# SRAM_Flash.net
KiCad netlist of a schematic drawn in Altium Designer
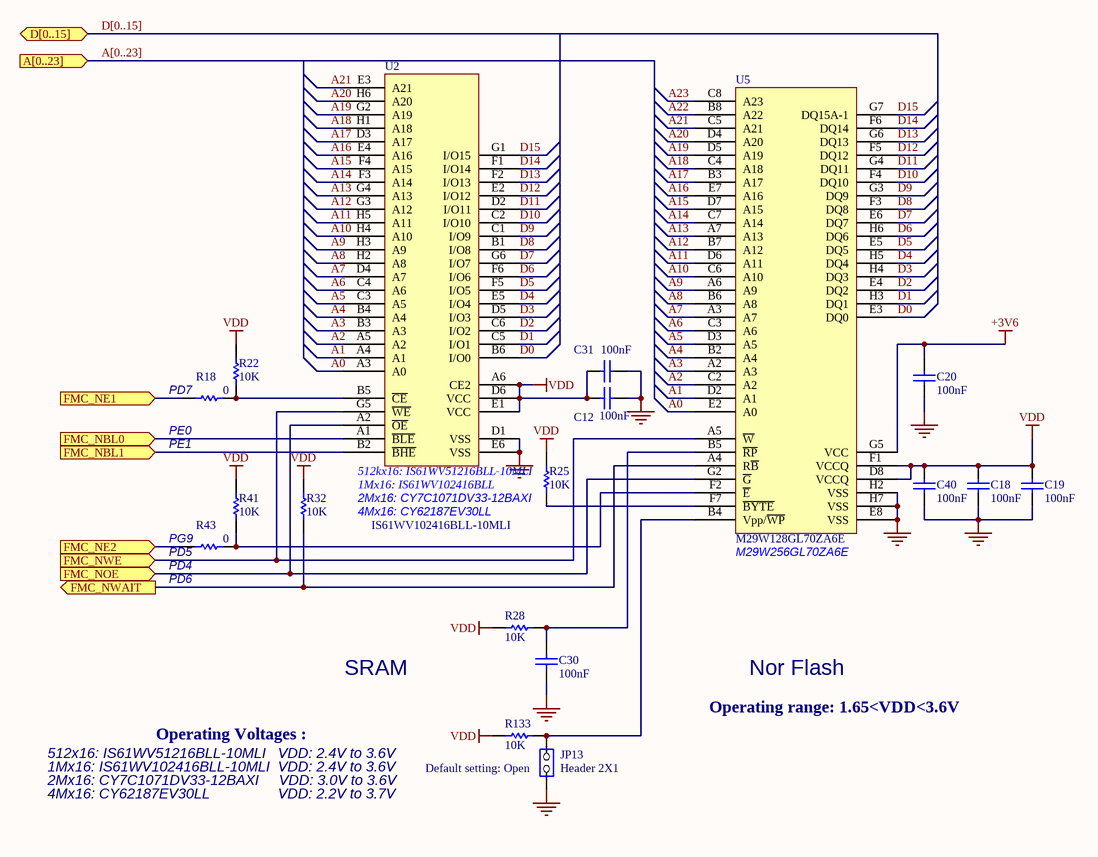
[diagram p0: SRAM&Flash.SchDoc]

(export (version "E")
  (design (tool "Eeschema 10.0.6"))
  (components
    (comp (ref "C12")
      (value "100nF")
      (footprint "0402C")
      (description "Capacitor")
      (fields (field (name "PUBLISHER") "Altium Limited"))
      (libsource (lib "Miscellaneous Devices") (part "Cap"))
    )
    (comp (ref "C18")
      (value "100nF")
      (footprint "0402C")
      (description "Capacitor")
      (fields (field (name "PUBLISHER") "Altium Limited"))
      (libsource (lib "Miscellaneous Devices") (part "Cap"))
    )
    (comp (ref "C19")
      (value "100nF")
      (footprint "0402C")
      (description "Capacitor")
      (fields (field (name "PUBLISHER") "Altium Limited"))
      (libsource (lib "Miscellaneous Devices") (part "Cap"))
    )
    (comp (ref "C20")
      (value "100nF")
      (footprint "0402C")
      (description "Capacitor")
      (fields (field (name "PUBLISHER") "Altium Limited"))
      (libsource (lib "Miscellaneous Devices") (part "Cap"))
    )
    (comp (ref "C30")
      (value "100nF")
      (footprint "0402C")
      (description "Capacitor")
      (fields (field (name "PUBLISHER") "Altium Limited"))
      (libsource (lib "Miscellaneous Devices") (part "Cap"))
    )
    (comp (ref "C31")
      (value "100nF")
      (footprint "0402C")
      (description "Capacitor")
      (fields (field (name "PUBLISHER") "Altium Limited"))
      (libsource (lib "Miscellaneous Devices") (part "Cap"))
    )
    (comp (ref "C40")
      (value "100nF")
      (footprint "0402C")
      (description "Capacitor")
      (fields (field (name "PUBLISHER") "Altium Limited"))
      (libsource (lib "Miscellaneous Devices") (part "Cap"))
    )
    (comp (ref "JP13") (value "Header 2X1") (footprint "SIP2") (libsource (lib "*") (part "JP2")))
    (comp (ref "R18")
      (value "0")
      (footprint "0603R")
      (description "Resistor")
      (fields (field (name "PUBLISHER") "Altium Limited"))
      (libsource (lib "Miscellaneous Devices") (part "Res1"))
    )
    (comp (ref "R22")
      (value "10K")
      (footprint "0402R")
      (description "Resistor")
      (fields (field (name "PUBLISHER") "Altium Limited"))
      (libsource (lib "Miscellaneous Devices") (part "res1"))
    )
    (comp (ref "R25")
      (value "10K")
      (footprint "0402R")
      (description "Resistor")
      (fields (field (name "PUBLISHER") "Altium Limited"))
      (libsource (lib "Miscellaneous Devices") (part "res1"))
    )
    (comp (ref "R28")
      (value "10K")
      (footprint "0402R")
      (description "Resistor")
      (fields (field (name "PUBLISHER") "Altium Limited"))
      (libsource (lib "Miscellaneous Devices") (part "res1"))
    )
    (comp (ref "R32")
      (value "10K")
      (footprint "0402R")
      (description "Resistor")
      (fields (field (name "PUBLISHER") "Altium Limited"))
      (libsource (lib "Miscellaneous Devices") (part "res1"))
    )
    (comp (ref "R41")
      (value "10K")
      (footprint "0402R")
      (description "Resistor")
      (fields (field (name "PUBLISHER") "Altium Limited"))
      (libsource (lib "Miscellaneous Devices") (part "res1"))
    )
    (comp (ref "R43")
      (value "0")
      (footprint "0603R")
      (description "Resistor")
      (fields (field (name "PUBLISHER") "Altium Limited"))
      (libsource (lib "Miscellaneous Devices") (part "Res1"))
    )
    (comp (ref "R133")
      (value "10K")
      (footprint "0402R")
      (description "Resistor")
      (fields (field (name "PUBLISHER") "Altium Limited"))
      (libsource (lib "Miscellaneous Devices") (part "res1"))
    )
    (comp (ref "U2")
      (value "IS61WV102416BLL-10MLI")
      (footprint "BGA48_0R75_9X11")
      (libsource (lib "MB1144_4") (part "SRAM_4Mx16"))
    )
    (comp (ref "U5")
      (value "M29W128GL70ZA6E")
      (footprint "BGA64_1_10X13")
      (libsource (lib "MB964") (part "M29W128FL70ZA6E"))
    )
  )
  (nets
    (net (code "1") (name "+3V6") (class "Default")
      (node (ref "C20") (pin "1") (pinfunction "1_1") (pintype "passive"))
      (node (ref "U5") (pin "G5") (pinfunction "VCC_G5") (pintype "passive"))
    )
    (net (code "2") (name "/A0") (class "Default")
      (node (ref "U2") (pin "A3") (pinfunction "A0_A3") (pintype "passive"))
      (node (ref "U5") (pin "E2") (pinfunction "A0_E2") (pintype "passive"))
    )
    (net (code "3") (name "/A1") (class "Default")
      (node (ref "U2") (pin "A4") (pinfunction "A1_A4") (pintype "passive"))
      (node (ref "U5") (pin "D2") (pinfunction "A1_D2") (pintype "passive"))
    )
    (net (code "4") (name "/A2") (class "Default")
      (node (ref "U2") (pin "A5") (pinfunction "A2_A5") (pintype "passive"))
      (node (ref "U5") (pin "C2") (pinfunction "A2_C2") (pintype "passive"))
    )
    (net (code "5") (name "/A3") (class "Default")
      (node (ref "U2") (pin "B3") (pinfunction "A3_B3") (pintype "passive"))
      (node (ref "U5") (pin "A2") (pinfunction "A3_A2") (pintype "passive"))
    )
    (net (code "6") (name "/A4") (class "Default")
      (node (ref "U2") (pin "B4") (pinfunction "A4_B4") (pintype "passive"))
      (node (ref "U5") (pin "B2") (pinfunction "A4_B2") (pintype "passive"))
    )
    (net (code "7") (name "/A5") (class "Default")
      (node (ref "U2") (pin "C3") (pinfunction "A5_C3") (pintype "passive"))
      (node (ref "U5") (pin "D3") (pinfunction "A5_D3") (pintype "passive"))
    )
    (net (code "8") (name "/A6") (class "Default")
      (node (ref "U2") (pin "C4") (pinfunction "A6_C4") (pintype "passive"))
      (node (ref "U5") (pin "C3") (pinfunction "A6_C3") (pintype "passive"))
    )
    (net (code "9") (name "/A7") (class "Default")
      (node (ref "U2") (pin "D4") (pinfunction "A7_D4") (pintype "passive"))
      (node (ref "U5") (pin "A3") (pinfunction "A7_A3") (pintype "passive"))
    )
    (net (code "10") (name "/A8") (class "Default")
      (node (ref "U2") (pin "H2") (pinfunction "A8_H2") (pintype "passive"))
      (node (ref "U5") (pin "B6") (pinfunction "A8_B6") (pintype "passive"))
    )
    (net (code "11") (name "/A9") (class "Default")
      (node (ref "U2") (pin "H3") (pinfunction "A9_H3") (pintype "passive"))
      (node (ref "U5") (pin "A6") (pinfunction "A9_A6") (pintype "passive"))
    )
    (net (code "12") (name "/A10") (class "Default")
      (node (ref "U2") (pin "H4") (pinfunction "A10_H4") (pintype "passive"))
      (node (ref "U5") (pin "C6") (pinfunction "A10_C6") (pintype "passive"))
    )
    (net (code "13") (name "/A11") (class "Default")
      (node (ref "U2") (pin "H5") (pinfunction "A11_H5") (pintype "passive"))
      (node (ref "U5") (pin "D6") (pinfunction "A11_D6") (pintype "passive"))
    )
    (net (code "14") (name "/A12") (class "Default")
      (node (ref "U2") (pin "G3") (pinfunction "A12_G3") (pintype "passive"))
      (node (ref "U5") (pin "B7") (pinfunction "A12_B7") (pintype "passive"))
    )
    (net (code "15") (name "/A13") (class "Default")
      (node (ref "U2") (pin "G4") (pinfunction "A13_G4") (pintype "passive"))
      (node (ref "U5") (pin "A7") (pinfunction "A13_A7") (pintype "passive"))
    )
    (net (code "16") (name "/A14") (class "Default")
      (node (ref "U2") (pin "F3") (pinfunction "A14_F3") (pintype "passive"))
      (node (ref "U5") (pin "C7") (pinfunction "A14_C7") (pintype "passive"))
    )
    (net (code "17") (name "/A15") (class "Default")
      (node (ref "U2") (pin "F4") (pinfunction "A15_F4") (pintype "passive"))
      (node (ref "U5") (pin "D7") (pinfunction "A15_D7") (pintype "passive"))
    )
    (net (code "18") (name "/A16") (class "Default")
      (node (ref "U2") (pin "E4") (pinfunction "A16_E4") (pintype "passive"))
      (node (ref "U5") (pin "E7") (pinfunction "A16_E7") (pintype "passive"))
    )
    (net (code "19") (name "/A17") (class "Default")
      (node (ref "U2") (pin "D3") (pinfunction "A17_D3") (pintype "passive"))
      (node (ref "U5") (pin "B3") (pinfunction "A17_B3") (pintype "passive"))
    )
    (net (code "20") (name "/A18") (class "Default")
      (node (ref "U2") (pin "H1") (pinfunction "A18_H1") (pintype "passive"))
      (node (ref "U5") (pin "C4") (pinfunction "A18_C4") (pintype "passive"))
    )
    (net (code "21") (name "/A19") (class "Default")
      (node (ref "U2") (pin "G2") (pinfunction "A19_G2") (pintype "passive"))
      (node (ref "U5") (pin "D5") (pinfunction "A19_D5") (pintype "passive"))
    )
    (net (code "22") (name "/A20") (class "Default")
      (node (ref "U2") (pin "H6") (pinfunction "A20_H6") (pintype "passive"))
      (node (ref "U5") (pin "D4") (pinfunction "A20_D4") (pintype "passive"))
    )
    (net (code "23") (name "/A21") (class "Default")
      (node (ref "U2") (pin "E3") (pinfunction "A21_E3") (pintype "passive"))
      (node (ref "U5") (pin "C5") (pinfunction "A21_C5") (pintype "passive"))
    )
    (net (code "24") (name "/A22") (class "Default")
      (node (ref "U5") (pin "B8") (pinfunction "A22_B8") (pintype "passive"))
    )
    (net (code "25") (name "/A23") (class "Default")
      (node (ref "U5") (pin "C8") (pinfunction "A23_C8") (pintype "passive"))
    )
    (net (code "27") (name "/D0") (class "Default")
      (node (ref "U2") (pin "B6") (pinfunction "I/O0_B6") (pintype "passive"))
      (node (ref "U5") (pin "E3") (pinfunction "DQ0_E3") (pintype "passive"))
    )
    (net (code "28") (name "/D1") (class "Default")
      (node (ref "U2") (pin "C5") (pinfunction "I/O1_C5") (pintype "passive"))
      (node (ref "U5") (pin "H3") (pinfunction "DQ1_H3") (pintype "passive"))
    )
    (net (code "29") (name "/D2") (class "Default")
      (node (ref "U2") (pin "C6") (pinfunction "I/O2_C6") (pintype "passive"))
      (node (ref "U5") (pin "E4") (pinfunction "DQ2_E4") (pintype "passive"))
    )
    (net (code "30") (name "/D3") (class "Default")
      (node (ref "U2") (pin "D5") (pinfunction "I/O3_D5") (pintype "passive"))
      (node (ref "U5") (pin "H4") (pinfunction "DQ3_H4") (pintype "passive"))
    )
    (net (code "31") (name "/D4") (class "Default")
      (node (ref "U2") (pin "E5") (pinfunction "I/O4_E5") (pintype "passive"))
      (node (ref "U5") (pin "H5") (pinfunction "DQ4_H5") (pintype "passive"))
    )
    (net (code "32") (name "/D5") (class "Default")
      (node (ref "U2") (pin "F5") (pinfunction "I/O5_F5") (pintype "passive"))
      (node (ref "U5") (pin "E5") (pinfunction "DQ5_E5") (pintype "passive"))
    )
    (net (code "33") (name "/D6") (class "Default")
      (node (ref "U2") (pin "F6") (pinfunction "I/O6_F6") (pintype "passive"))
      (node (ref "U5") (pin "H6") (pinfunction "DQ6_H6") (pintype "passive"))
    )
    (net (code "34") (name "/D7") (class "Default")
      (node (ref "U2") (pin "G6") (pinfunction "I/O7_G6") (pintype "passive"))
      (node (ref "U5") (pin "E6") (pinfunction "DQ7_E6") (pintype "passive"))
    )
    (net (code "35") (name "/D8") (class "Default")
      (node (ref "U2") (pin "B1") (pinfunction "I/O8_B1") (pintype "passive"))
      (node (ref "U5") (pin "F3") (pinfunction "DQ8_F3") (pintype "passive"))
    )
    (net (code "36") (name "/D9") (class "Default")
      (node (ref "U2") (pin "C1") (pinfunction "I/O9_C1") (pintype "passive"))
      (node (ref "U5") (pin "G3") (pinfunction "DQ9_G3") (pintype "passive"))
    )
    (net (code "37") (name "/D10") (class "Default")
      (node (ref "U2") (pin "C2") (pinfunction "I/O10_C2") (pintype "passive"))
      (node (ref "U5") (pin "F4") (pinfunction "DQ10_F4") (pintype "passive"))
    )
    (net (code "38") (name "/D11") (class "Default")
      (node (ref "U2") (pin "D2") (pinfunction "I/O11_D2") (pintype "passive"))
      (node (ref "U5") (pin "G4") (pinfunction "DQ11_G4") (pintype "passive"))
    )
    (net (code "39") (name "/D12") (class "Default")
      (node (ref "U2") (pin "E2") (pinfunction "I/O12_E2") (pintype "passive"))
      (node (ref "U5") (pin "F5") (pinfunction "DQ12_F5") (pintype "passive"))
    )
    (net (code "40") (name "/D13") (class "Default")
      (node (ref "U2") (pin "F2") (pinfunction "I/O13_F2") (pintype "passive"))
      (node (ref "U5") (pin "G6") (pinfunction "DQ13_G6") (pintype "passive"))
    )
    (net (code "41") (name "/D14") (class "Default")
      (node (ref "U2") (pin "F1") (pinfunction "I/O14_F1") (pintype "passive"))
      (node (ref "U5") (pin "F6") (pinfunction "DQ14_F6") (pintype "passive"))
    )
    (net (code "42") (name "/D15") (class "Default")
      (node (ref "U2") (pin "G1") (pinfunction "I/O15_G1") (pintype "passive"))
      (node (ref "U5") (pin "G7") (pinfunction "DQ15A-1_G7") (pintype "passive"))
    )
    (net (code "44") (name "/FMC_NBL0") (class "Default")
      (node (ref "U2") (pin "A1") (pinfunction "~{BLE}_A1") (pintype "passive"))
    )
    (net (code "45") (name "/FMC_NBL1") (class "Default")
      (node (ref "U2") (pin "B2") (pinfunction "~{BHE}_B2") (pintype "passive"))
    )
    (net (code "46") (name "/FMC_NE1") (class "Default")
      (node (ref "R18") (pin "2") (pinfunction "2_2") (pintype "passive"))
    )
    (net (code "47") (name "/FMC_NE2") (class "Default")
      (node (ref "R43") (pin "2") (pinfunction "2_2") (pintype "passive"))
    )
    (net (code "48") (name "/FMC_NOE") (class "Default")
      (node (ref "U2") (pin "A2") (pinfunction "~{OE}_A2") (pintype "passive"))
      (node (ref "U5") (pin "G2") (pinfunction "~{G}_G2") (pintype "passive"))
    )
    (net (code "49") (name "/FMC_NWAIT") (class "Default")
      (node (ref "R32") (pin "2") (pinfunction "2_2") (pintype "passive"))
      (node (ref "U5") (pin "A4") (pinfunction "R~{B}_A4") (pintype "passive"))
    )
    (net (code "50") (name "/FMC_NWE") (class "Default")
      (node (ref "U2") (pin "G5") (pinfunction "~{WE}_G5") (pintype "passive"))
      (node (ref "U5") (pin "A5") (pinfunction "~{W}_A5") (pintype "passive"))
    )
    (net (code "51") (name "GND") (class "Default")
      (node (ref "C12") (pin "2") (pinfunction "2_2") (pintype "passive"))
      (node (ref "C18") (pin "2") (pinfunction "2_2") (pintype "passive"))
      (node (ref "C19") (pin "2") (pinfunction "2_2") (pintype "passive"))
      (node (ref "C20") (pin "2") (pinfunction "2_2") (pintype "passive"))
      (node (ref "C30") (pin "2") (pinfunction "2_2") (pintype "passive"))
      (node (ref "C31") (pin "2") (pinfunction "2_2") (pintype "passive"))
      (node (ref "C40") (pin "2") (pinfunction "2_2") (pintype "passive"))
      (node (ref "JP13") (pin "1") (pinfunction "COMMON_1") (pintype "passive"))
      (node (ref "U2") (pin "D1") (pinfunction "VSS_D1") (pintype "passive"))
      (node (ref "U2") (pin "E6") (pinfunction "VSS_E6") (pintype "passive"))
      (node (ref "U5") (pin "E8") (pinfunction "VSS_E8") (pintype "passive"))
      (node (ref "U5") (pin "H2") (pinfunction "VSS_H2") (pintype "passive"))
      (node (ref "U5") (pin "H7") (pinfunction "VSS_H7") (pintype "passive"))
    )
    (net (code "52") (name "Net-(JP13-NO)") (class "Default")
      (node (ref "JP13") (pin "2") (pinfunction "NO_2") (pintype "passive"))
      (node (ref "R133") (pin "2") (pinfunction "2_2") (pintype "passive"))
      (node (ref "U5") (pin "B4") (pinfunction "Vpp/~{WP}_B4") (pintype "passive"))
    )
    (net (code "53") (name "Net-(U2-~{CE})") (class "Default")
      (node (ref "R18") (pin "1") (pinfunction "1_1") (pintype "passive"))
      (node (ref "R22") (pin "2") (pinfunction "2_2") (pintype "passive"))
      (node (ref "U2") (pin "B5") (pinfunction "~{CE}_B5") (pintype "passive"))
    )
    (net (code "54") (name "Net-(U5-~{BYTE})") (class "Default")
      (node (ref "R25") (pin "2") (pinfunction "2_2") (pintype "passive"))
      (node (ref "U5") (pin "F7") (pinfunction "~{BYTE}_F7") (pintype "passive"))
    )
    (net (code "55") (name "Net-(U5-~{E})") (class "Default")
      (node (ref "R41") (pin "2") (pinfunction "2_2") (pintype "passive"))
      (node (ref "R43") (pin "1") (pinfunction "1_1") (pintype "passive"))
      (node (ref "U5") (pin "F2") (pinfunction "~{E}_F2") (pintype "passive"))
    )
    (net (code "56") (name "Net-(U5-~{RP})") (class "Default")
      (node (ref "C30") (pin "1") (pinfunction "1_1") (pintype "passive"))
      (node (ref "R28") (pin "2") (pinfunction "2_2") (pintype "passive"))
      (node (ref "U5") (pin "B5") (pinfunction "~{RP}_B5") (pintype "passive"))
    )
    (net (code "57") (name "VDD") (class "Default")
      (node (ref "C12") (pin "1") (pinfunction "1_1") (pintype "passive"))
      (node (ref "C18") (pin "1") (pinfunction "1_1") (pintype "passive"))
      (node (ref "C19") (pin "1") (pinfunction "1_1") (pintype "passive"))
      (node (ref "C31") (pin "1") (pinfunction "1_1") (pintype "passive"))
      (node (ref "C40") (pin "1") (pinfunction "1_1") (pintype "passive"))
      (node (ref "R133") (pin "1") (pinfunction "1_1") (pintype "passive"))
      (node (ref "R22") (pin "1") (pinfunction "1_1") (pintype "passive"))
      (node (ref "R25") (pin "1") (pinfunction "1_1") (pintype "passive"))
      (node (ref "R28") (pin "1") (pinfunction "1_1") (pintype "passive"))
      (node (ref "R32") (pin "1") (pinfunction "1_1") (pintype "passive"))
      (node (ref "R41") (pin "1") (pinfunction "1_1") (pintype "passive"))
      (node (ref "U2") (pin "A6") (pinfunction "CE2_A6") (pintype "passive"))
      (node (ref "U2") (pin "D6") (pinfunction "VCC_D6") (pintype "passive"))
      (node (ref "U2") (pin "E1") (pinfunction "VCC_E1") (pintype "passive"))
      (node (ref "U5") (pin "D8") (pinfunction "VCCQ_D8") (pintype "passive"))
      (node (ref "U5") (pin "F1") (pinfunction "VCCQ_F1") (pintype "passive"))
    )
  )
)
